# LightStickPower.net
KiCad netlist of a schematic drawn in EAGLE
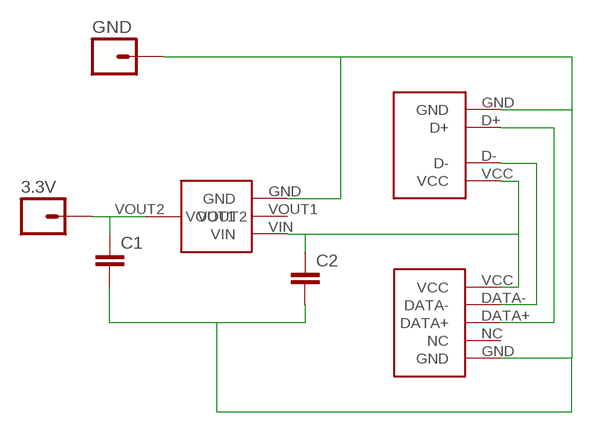
[diagram p0: schematic, sheet 1]

(export (version "E")
  (design (tool "Eeschema 10.0.6"))
  (components
    (comp (ref "3.3V")
      (value "M01PTH")
      (footprint "eagle-import:1X01")
      (libsource (lib "eagle-import") (part "M01PTH"))
    )
    (comp (ref "C1")
      (value "CAP0805")
      (footprint "eagle-import:0805")
      (libsource (lib "eagle-import") (part "CAP0805"))
    )
    (comp (ref "C2")
      (value "CAP0805")
      (footprint "eagle-import:0805")
      (libsource (lib "eagle-import") (part "CAP0805"))
    )
    (comp (ref "GND")
      (value "M01PTH")
      (footprint "eagle-import:1X01")
      (libsource (lib "eagle-import") (part "M01PTH"))
    )
    (comp (ref "USB1")
      (value "USB_A_932")
      (footprint "eagle-import:USB_A_932")
      (libsource (lib "eagle-import") (part "USB_A_932"))
    )
    (comp (ref "USB2")
      (value "USB_MICROB_PLUG_ZX64_B_5S")
      (footprint "eagle-import:USB_MICROB_PLUG_ZX64_B_5S")
      (libsource (lib "eagle-import") (part "USB_MICROB_PLUG_ZX64_B_5S"))
    )
    (comp (ref "V1")
      (value "VOLTAGE_REGULATOR_AP2114H")
      (footprint "eagle-import:SOT-223")
      (libsource (lib "eagle-import") (part "VOLTAGE_REGULATOR_AP2114H"))
    )
  )
  (nets
    (net (code "1") (name "Net-(3.3V-Pad1)") (class "Default")
      (node (ref "3.3V") (pin "1") (pinfunction "1_1") (pintype "passive"))
      (node (ref "C1") (pin "1") (pinfunction "1_1") (pintype "passive"))
      (node (ref "V1") (pin "VOUT2") (pinfunction "VOUT2_VOUT2") (pintype "bidirectional"))
    )
    (net (code "2") (name "Net-(C1-Pad2)") (class "Default")
      (node (ref "C1") (pin "2") (pinfunction "2_2") (pintype "passive"))
      (node (ref "C2") (pin "2") (pinfunction "2_2") (pintype "passive"))
      (node (ref "GND") (pin "1") (pinfunction "1_1") (pintype "passive"))
      (node (ref "USB1") (pin "GND") (pinfunction "GND_GND") (pintype "bidirectional"))
      (node (ref "USB2") (pin "GND") (pinfunction "GND_GND") (pintype "bidirectional"))
      (node (ref "V1") (pin "GND") (pinfunction "GND_GND") (pintype "bidirectional"))
    )
    (net (code "3") (name "Net-(C2-Pad1)") (class "Default")
      (node (ref "C2") (pin "1") (pinfunction "1_1") (pintype "passive"))
      (node (ref "USB1") (pin "VCC") (pinfunction "VCC_VCC") (pintype "bidirectional"))
      (node (ref "USB2") (pin "VCC") (pinfunction "VCC_VCC") (pintype "bidirectional"))
      (node (ref "V1") (pin "VIN") (pinfunction "VIN_VIN") (pintype "bidirectional"))
    )
    (net (code "4") (name "Net-(USB1-PadD+)") (class "Default")
      (node (ref "USB1") (pin "D+") (pinfunction "D+_D+") (pintype "bidirectional"))
      (node (ref "USB2") (pin "DATA+") (pinfunction "DATA+_DATA+") (pintype "bidirectional"))
    )
    (net (code "5") (name "Net-(USB1-PadD-)") (class "Default")
      (node (ref "USB1") (pin "D-") (pinfunction "D-_D-") (pintype "bidirectional"))
      (node (ref "USB2") (pin "DATA-") (pinfunction "DATA-_DATA-") (pintype "bidirectional"))
    )
    (net (code "6") (name "unconnected-(USB2-PadNC)") (class "Default")
      (node (ref "USB2") (pin "NC") (pinfunction "NC_NC") (pintype "bidirectional"))
    )
    (net (code "7") (name "unconnected-(V1-PadVOUT1)") (class "Default")
      (node (ref "V1") (pin "VOUT1") (pinfunction "VOUT1_VOUT1") (pintype "bidirectional"))
    )
  )
)
